# mcu.net
KiCad netlist of a schematic drawn in Altium Designer
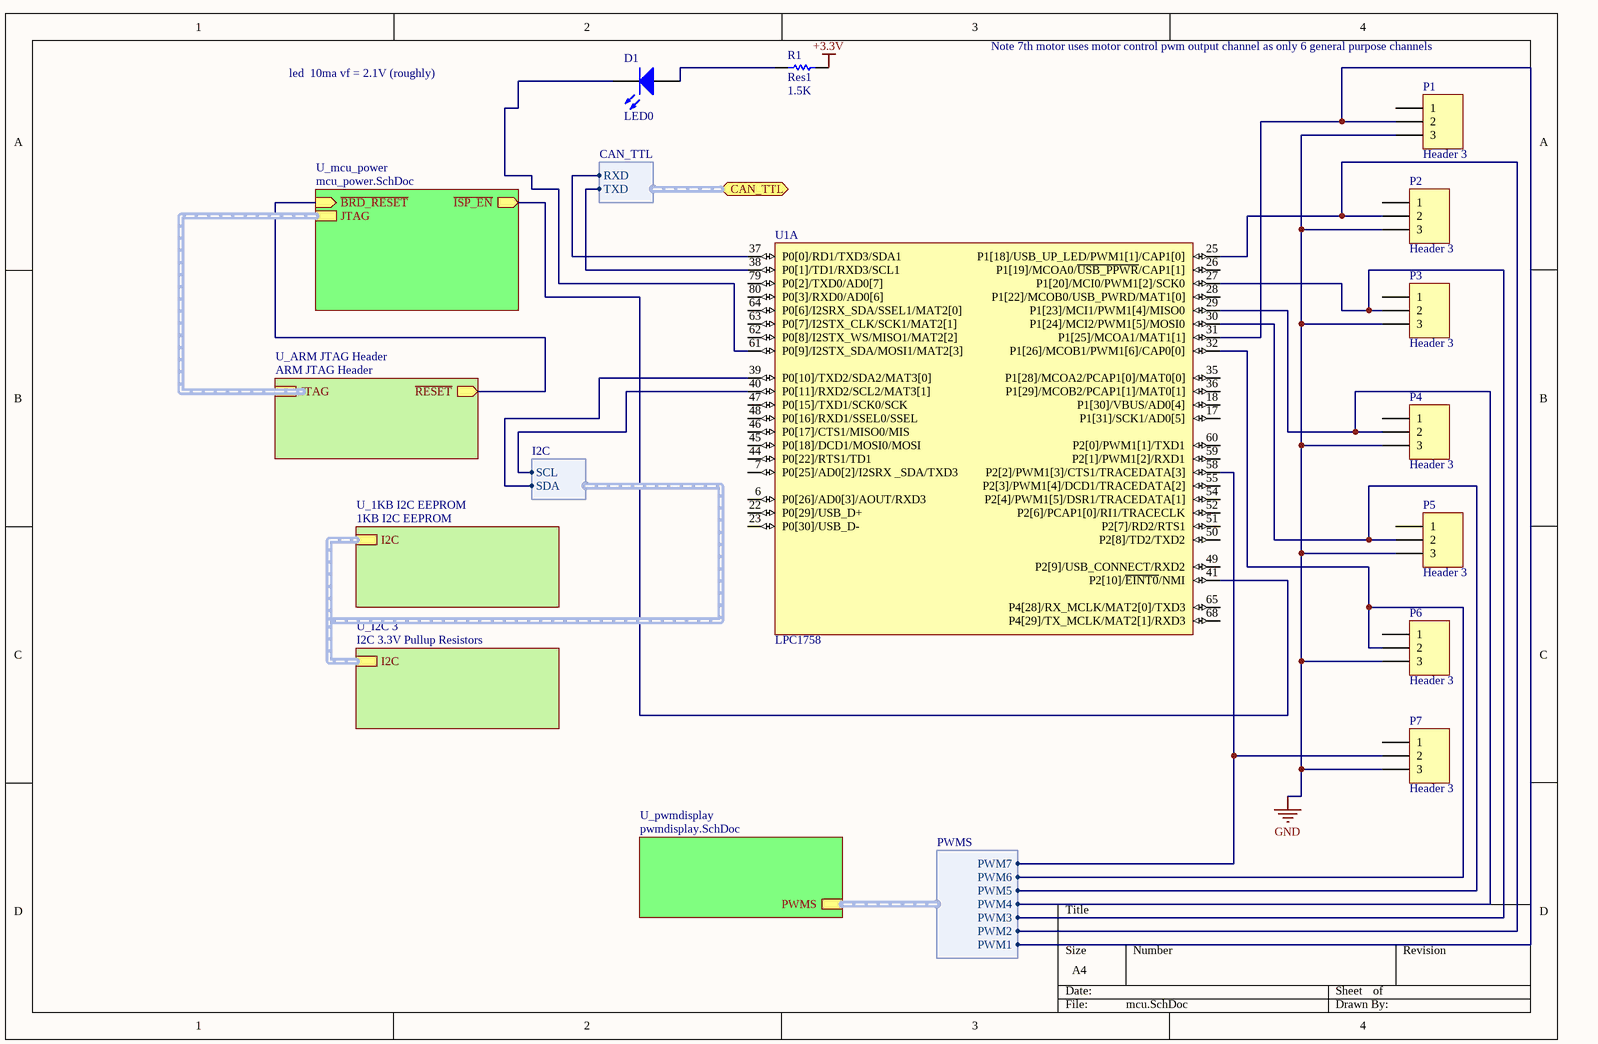
[diagram p0: mcu.SchDoc]

(export (version "E")
  (design (tool "Eeschema 10.0.6"))
  (components
    (comp (ref "D1")
      (value "LED0")
      (footprint "LGQ971")
      (description "Typical INFRARED GaAs LED")
      (fields (field (name "PUBLISHER") "Altium Limited"))
      (libsource (lib "Miscellaneous Devices") (part "LED0"))
    )
    (comp (ref "P1")
      (value "Header 3")
      (footprint "HDR1X3")
      (description "Header, 3-Pin")
      (fields (field (name "PUBLISHER") "Altium Limited"))
      (libsource (lib "Miscellaneous Connectors") (part "Header 3"))
    )
    (comp (ref "P2")
      (value "Header 3")
      (footprint "HDR1X3")
      (description "Header, 3-Pin")
      (fields (field (name "PUBLISHER") "Altium Limited"))
      (libsource (lib "Miscellaneous Connectors") (part "Header 3"))
    )
    (comp (ref "P3")
      (value "Header 3")
      (footprint "HDR1X3")
      (description "Header, 3-Pin")
      (fields (field (name "PUBLISHER") "Altium Limited"))
      (libsource (lib "Miscellaneous Connectors") (part "Header 3"))
    )
    (comp (ref "P4")
      (value "Header 3")
      (footprint "HDR1X3")
      (description "Header, 3-Pin")
      (fields (field (name "PUBLISHER") "Altium Limited"))
      (libsource (lib "Miscellaneous Connectors") (part "Header 3"))
    )
    (comp (ref "P5")
      (value "Header 3")
      (footprint "HDR1X3")
      (description "Header, 3-Pin")
      (fields (field (name "PUBLISHER") "Altium Limited"))
      (libsource (lib "Miscellaneous Connectors") (part "Header 3"))
    )
    (comp (ref "P6")
      (value "Header 3")
      (footprint "HDR1X3")
      (description "Header, 3-Pin")
      (fields (field (name "PUBLISHER") "Altium Limited"))
      (libsource (lib "Miscellaneous Connectors") (part "Header 3"))
    )
    (comp (ref "P7")
      (value "Header 3")
      (footprint "HDR1X3")
      (description "Header, 3-Pin")
      (fields (field (name "PUBLISHER") "Altium Limited"))
      (libsource (lib "Miscellaneous Connectors") (part "Header 3"))
    )
    (comp (ref "R1")
      (value "Res1")
      (footprint "AXIAL-0.3")
      (description "Resistor")
      (fields (field (name "ALTIUM_VALUE") "1.5K") (field (name "PUBLISHER") "Altium Limited"))
      (libsource (lib "Miscellaneous Devices") (part "Res1"))
    )
    (comp (ref "U1")
      (value "LPC1758")
      (footprint "LPC1758FBD80")
      (description "NXP - LPC1758FBD80 - MCU, 32BIT, ARM CORTEX M3, 80LQFP")
      (libsource (lib "LPC1758") (part "LPC1758"))
    )
  )
  (nets
    (net (code "4") (name "+3.3V") (class "Default")
      (node (ref "R1") (pin "2") (pinfunction "2_2") (pintype "passive"))
    )
    (net (code "6") (name "/PWM1") (class "Default")
      (node (ref "P1") (pin "2") (pinfunction "2_2") (pintype "passive"))
      (node (ref "U1") (pin "31") (pinfunction "P1[25]/MCOA1/MAT1[1]_31") (pintype "bidirectional"))
    )
    (net (code "7") (name "/PWM2") (class "Default")
      (node (ref "P2") (pin "2") (pinfunction "2_2") (pintype "passive"))
      (node (ref "U1") (pin "25") (pinfunction "P1[18]/USB_UP_LED/PWM1[1]/CAP1[0]_25") (pintype "bidirectional"))
    )
    (net (code "8") (name "/PWM3") (class "Default")
      (node (ref "P3") (pin "2") (pinfunction "2_2") (pintype "passive"))
      (node (ref "U1") (pin "27") (pinfunction "P1[20]/MCI0/PWM1[2]/SCK0_27") (pintype "bidirectional"))
    )
    (net (code "9") (name "/PWM4") (class "Default")
      (node (ref "P4") (pin "2") (pinfunction "2_2") (pintype "passive"))
      (node (ref "U1") (pin "29") (pinfunction "P1[23]/MCI1/PWM1[4]/MISO0_29") (pintype "bidirectional"))
    )
    (net (code "10") (name "/PWM5") (class "Default")
      (node (ref "P5") (pin "2") (pinfunction "2_2") (pintype "passive"))
      (node (ref "U1") (pin "30") (pinfunction "P1[24]/MCI2/PWM1[5]/MOSI0_30") (pintype "bidirectional"))
    )
    (net (code "11") (name "/PWM6") (class "Default")
      (node (ref "P6") (pin "2") (pinfunction "2_2") (pintype "passive"))
      (node (ref "U1") (pin "32") (pinfunction "P1[26]/MCOB1/PWM1[6]/CAP0[0]_32") (pintype "bidirectional"))
    )
    (net (code "12") (name "/PWM7") (class "Default")
      (node (ref "P7") (pin "2") (pinfunction "2_2") (pintype "passive"))
      (node (ref "U1") (pin "58") (pinfunction "P2[2]/PWM1[3]/CTS1/TRACEDATA[3]_58") (pintype "bidirectional"))
    )
    (net (code "13") (name "/RXD") (class "Default")
      (node (ref "U1") (pin "37") (pinfunction "P0[0]/RD1/TXD3/SDA1_37") (pintype "bidirectional"))
    )
    (net (code "14") (name "/SCL") (class "Default")
      (node (ref "U1") (pin "40") (pinfunction "P0[11]/RXD2/SCL2/MAT3[1]_40") (pintype "bidirectional"))
    )
    (net (code "15") (name "/SDA") (class "Default")
      (node (ref "U1") (pin "39") (pinfunction "P0[10]/TXD2/SDA2/MAT3[0]_39") (pintype "bidirectional"))
    )
    (net (code "16") (name "/TXD") (class "Default")
      (node (ref "U1") (pin "38") (pinfunction "P0[1]/TD1/RXD3/SCL1_38") (pintype "bidirectional"))
    )
    (net (code "20") (name "/~{ISP_EN}") (class "Default")
      (node (ref "U1") (pin "41") (pinfunction "P2[10]/~{EINT0}/NMI_41") (pintype "bidirectional"))
    )
    (net (code "22") (name "GND") (class "Default")
      (node (ref "P1") (pin "3") (pinfunction "3_3") (pintype "passive"))
      (node (ref "P2") (pin "3") (pinfunction "3_3") (pintype "passive"))
      (node (ref "P3") (pin "3") (pinfunction "3_3") (pintype "passive"))
      (node (ref "P4") (pin "3") (pinfunction "3_3") (pintype "passive"))
      (node (ref "P5") (pin "3") (pinfunction "3_3") (pintype "passive"))
      (node (ref "P6") (pin "3") (pinfunction "3_3") (pintype "passive"))
      (node (ref "P7") (pin "3") (pinfunction "3_3") (pintype "passive"))
    )
    (net (code "23") (name "Net-(D1-A)") (class "Default")
      (node (ref "D1") (pin "1") (pinfunction "A_1") (pintype "passive"))
      (node (ref "R1") (pin "1") (pinfunction "1_1") (pintype "passive"))
    )
    (net (code "24") (name "Net-(D1-K)") (class "Default")
      (node (ref "D1") (pin "2") (pinfunction "K_2") (pintype "passive"))
      (node (ref "U1") (pin "61") (pinfunction "P0[9]/I2STX_SDA/MOSI1/MAT2[3]_61") (pintype "bidirectional"))
    )
    (net (code "25") (name "unconnected-(P1-Pad1)") (class "Default")
      (node (ref "P1") (pin "1") (pinfunction "1_1") (pintype "passive"))
    )
    (net (code "26") (name "unconnected-(P2-Pad1)") (class "Default")
      (node (ref "P2") (pin "1") (pinfunction "1_1") (pintype "passive"))
    )
    (net (code "27") (name "unconnected-(P3-Pad1)") (class "Default")
      (node (ref "P3") (pin "1") (pinfunction "1_1") (pintype "passive"))
    )
    (net (code "28") (name "unconnected-(P4-Pad1)") (class "Default")
      (node (ref "P4") (pin "1") (pinfunction "1_1") (pintype "passive"))
    )
    (net (code "29") (name "unconnected-(P5-Pad1)") (class "Default")
      (node (ref "P5") (pin "1") (pinfunction "1_1") (pintype "passive"))
    )
    (net (code "30") (name "unconnected-(P6-Pad1)") (class "Default")
      (node (ref "P6") (pin "1") (pinfunction "1_1") (pintype "passive"))
    )
    (net (code "31") (name "unconnected-(P7-Pad1)") (class "Default")
      (node (ref "P7") (pin "1") (pinfunction "1_1") (pintype "passive"))
    )
    (net (code "32") (name "unconnected-(U1A-P0[2]{slash}TXD0{slash}AD0[7]-Pad79)") (class "Default")
      (node (ref "U1") (pin "79") (pinfunction "P0[2]/TXD0/AD0[7]_79") (pintype "bidirectional"))
    )
    (net (code "33") (name "unconnected-(U1A-P0[3]{slash}RXD0{slash}AD0[6]-Pad80)") (class "Default")
      (node (ref "U1") (pin "80") (pinfunction "P0[3]/RXD0/AD0[6]_80") (pintype "bidirectional"))
    )
    (net (code "34") (name "unconnected-(U1A-P0[6]{slash}I2SRX_SDA{slash}SSEL1{slash}MAT2[0]-Pad64)") (class "Default")
      (node (ref "U1") (pin "64") (pinfunction "P0[6]/I2SRX_SDA/SSEL1/MAT2[0]_64") (pintype "bidirectional"))
    )
    (net (code "35") (name "unconnected-(U1A-P0[7]{slash}I2STX_CLK{slash}SCK1{slash}MAT2[1]-Pad63)") (class "Default")
      (node (ref "U1") (pin "63") (pinfunction "P0[7]/I2STX_CLK/SCK1/MAT2[1]_63") (pintype "bidirectional"))
    )
    (net (code "36") (name "unconnected-(U1A-P0[8]{slash}I2STX_WS{slash}MISO1{slash}MAT2[2]-Pad62)") (class "Default")
      (node (ref "U1") (pin "62") (pinfunction "P0[8]/I2STX_WS/MISO1/MAT2[2]_62") (pintype "bidirectional"))
    )
    (net (code "37") (name "unconnected-(U1A-P0[15]{slash}TXD1{slash}SCK0{slash}SCK-Pad47)") (class "Default")
      (node (ref "U1") (pin "47") (pinfunction "P0[15]/TXD1/SCK0/SCK_47") (pintype "bidirectional"))
    )
    (net (code "38") (name "unconnected-(U1A-P0[16]{slash}RXD1{slash}SSEL0{slash}SSEL-Pad48)") (class "Default")
      (node (ref "U1") (pin "48") (pinfunction "P0[16]/RXD1/SSEL0/SSEL_48") (pintype "bidirectional"))
    )
    (net (code "39") (name "unconnected-(U1A-P0[17]{slash}CTS1{slash}MISO0{slash}MIS-Pad46)") (class "Default")
      (node (ref "U1") (pin "46") (pinfunction "P0[17]/CTS1/MISO0/MIS_46") (pintype "bidirectional"))
    )
    (net (code "40") (name "unconnected-(U1A-P0[18]{slash}DCD1{slash}MOSI0{slash}MOSI-Pad45)") (class "Default")
      (node (ref "U1") (pin "45") (pinfunction "P0[18]/DCD1/MOSI0/MOSI_45") (pintype "bidirectional"))
    )
    (net (code "41") (name "unconnected-(U1A-P0[22]{slash}RTS1{slash}TD1-Pad44)") (class "Default")
      (node (ref "U1") (pin "44") (pinfunction "P0[22]/RTS1/TD1_44") (pintype "bidirectional"))
    )
    (net (code "42") (name "unconnected-(U1A-P0[25]{slash}AD0[2]{slash}I2SRX__SDA{slash}TXD3-Pad7)") (class "Default")
      (node (ref "U1") (pin "7") (pinfunction "P0[25]/AD0[2]/I2SRX__SDA/TXD3_7") (pintype "bidirectional"))
    )
    (net (code "43") (name "unconnected-(U1A-P0[26]{slash}AD0[3]{slash}AOUT{slash}RXD3-Pad6)") (class "Default")
      (node (ref "U1") (pin "6") (pinfunction "P0[26]/AD0[3]/AOUT/RXD3_6") (pintype "bidirectional"))
    )
    (net (code "44") (name "unconnected-(U1A-P0[29]{slash}USB_D+-Pad22)") (class "Default")
      (node (ref "U1") (pin "22") (pinfunction "P0[29]/USB_D+_22") (pintype "bidirectional"))
    )
    (net (code "45") (name "unconnected-(U1A-P0[30]{slash}USB_D--Pad23)") (class "Default")
      (node (ref "U1") (pin "23") (pinfunction "P0[30]/USB_D-_23") (pintype "bidirectional"))
    )
    (net (code "46") (name "unconnected-(U1A-P1[19]{slash}MCOA0{slash}~{USB_PPWR}{slash}CAP1[1]-Pad26)") (class "Default")
      (node (ref "U1") (pin "26") (pinfunction "P1[19]/MCOA0/~{USB_PPWR}/CAP1[1]_26") (pintype "bidirectional"))
    )
    (net (code "47") (name "unconnected-(U1A-P1[22]{slash}MCOB0{slash}USB_PWRD{slash}MAT1[0]-Pad28)") (class "Default")
      (node (ref "U1") (pin "28") (pinfunction "P1[22]/MCOB0/USB_PWRD/MAT1[0]_28") (pintype "bidirectional"))
    )
    (net (code "48") (name "unconnected-(U1A-P1[28]{slash}MCOA2{slash}PCAP1[0]{slash}MAT0[0]-Pad35)") (class "Default")
      (node (ref "U1") (pin "35") (pinfunction "P1[28]/MCOA2/PCAP1[0]/MAT0[0]_35") (pintype "bidirectional"))
    )
    (net (code "49") (name "unconnected-(U1A-P1[29]{slash}MCOB2{slash}PCAP1[1]{slash}MAT0[1]-Pad36)") (class "Default")
      (node (ref "U1") (pin "36") (pinfunction "P1[29]/MCOB2/PCAP1[1]/MAT0[1]_36") (pintype "bidirectional"))
    )
    (net (code "50") (name "unconnected-(U1A-P1[30]{slash}VBUS{slash}AD0[4]-Pad18)") (class "Default")
      (node (ref "U1") (pin "18") (pinfunction "P1[30]/VBUS/AD0[4]_18") (pintype "bidirectional"))
    )
    (net (code "51") (name "unconnected-(U1A-P1[31]{slash}SCK1{slash}AD0[5]-Pad17)") (class "Default")
      (node (ref "U1") (pin "17") (pinfunction "P1[31]/SCK1/AD0[5]_17") (pintype "bidirectional"))
    )
    (net (code "52") (name "unconnected-(U1A-P2[0]{slash}PWM1[1]{slash}TXD1-Pad60)") (class "Default")
      (node (ref "U1") (pin "60") (pinfunction "P2[0]/PWM1[1]/TXD1_60") (pintype "bidirectional"))
    )
    (net (code "53") (name "unconnected-(U1A-P2[1]{slash}PWM1[2]{slash}RXD1-Pad59)") (class "Default")
      (node (ref "U1") (pin "59") (pinfunction "P2[1]/PWM1[2]/RXD1_59") (pintype "bidirectional"))
    )
    (net (code "54") (name "unconnected-(U1A-P2[3]{slash}PWM1[4]{slash}DCD1{slash}TRACEDATA[2]-Pad55)") (class "Default")
      (node (ref "U1") (pin "55") (pinfunction "P2[3]/PWM1[4]/DCD1/TRACEDATA[2]_55") (pintype "bidirectional"))
    )
    (net (code "55") (name "unconnected-(U1A-P2[4]{slash}PWM1[5]{slash}DSR1{slash}TRACEDATA[1]-Pad54)") (class "Default")
      (node (ref "U1") (pin "54") (pinfunction "P2[4]/PWM1[5]/DSR1/TRACEDATA[1]_54") (pintype "bidirectional"))
    )
    (net (code "56") (name "unconnected-(U1A-P2[6]{slash}PCAP1[0]{slash}RI1{slash}TRACECLK-Pad52)") (class "Default")
      (node (ref "U1") (pin "52") (pinfunction "P2[6]/PCAP1[0]/RI1/TRACECLK_52") (pintype "bidirectional"))
    )
    (net (code "57") (name "unconnected-(U1A-P2[7]{slash}RD2{slash}RTS1-Pad51)") (class "Default")
      (node (ref "U1") (pin "51") (pinfunction "P2[7]/RD2/RTS1_51") (pintype "bidirectional"))
    )
    (net (code "58") (name "unconnected-(U1A-P2[8]{slash}TD2{slash}TXD2-Pad50)") (class "Default")
      (node (ref "U1") (pin "50") (pinfunction "P2[8]/TD2/TXD2_50") (pintype "bidirectional"))
    )
    (net (code "59") (name "unconnected-(U1A-P2[9]{slash}USB_CONNECT{slash}RXD2-Pad49)") (class "Default")
      (node (ref "U1") (pin "49") (pinfunction "P2[9]/USB_CONNECT/RXD2_49") (pintype "bidirectional"))
    )
    (net (code "60") (name "unconnected-(U1A-P4[28]{slash}RX_MCLK{slash}MAT2[0]{slash}TXD3-Pad65)") (class "Default")
      (node (ref "U1") (pin "65") (pinfunction "P4[28]/RX_MCLK/MAT2[0]/TXD3_65") (pintype "bidirectional"))
    )
    (net (code "61") (name "unconnected-(U1A-P4[29]{slash}TX_MCLK{slash}MAT2[1]{slash}RXD3-Pad68)") (class "Default")
      (node (ref "U1") (pin "68") (pinfunction "P4[29]/TX_MCLK/MAT2[1]/RXD3_68") (pintype "bidirectional"))
    )
  )
)
